# Biped_Motor_Control_Board.net
KiCad netlist of a schematic drawn in EasyEDA
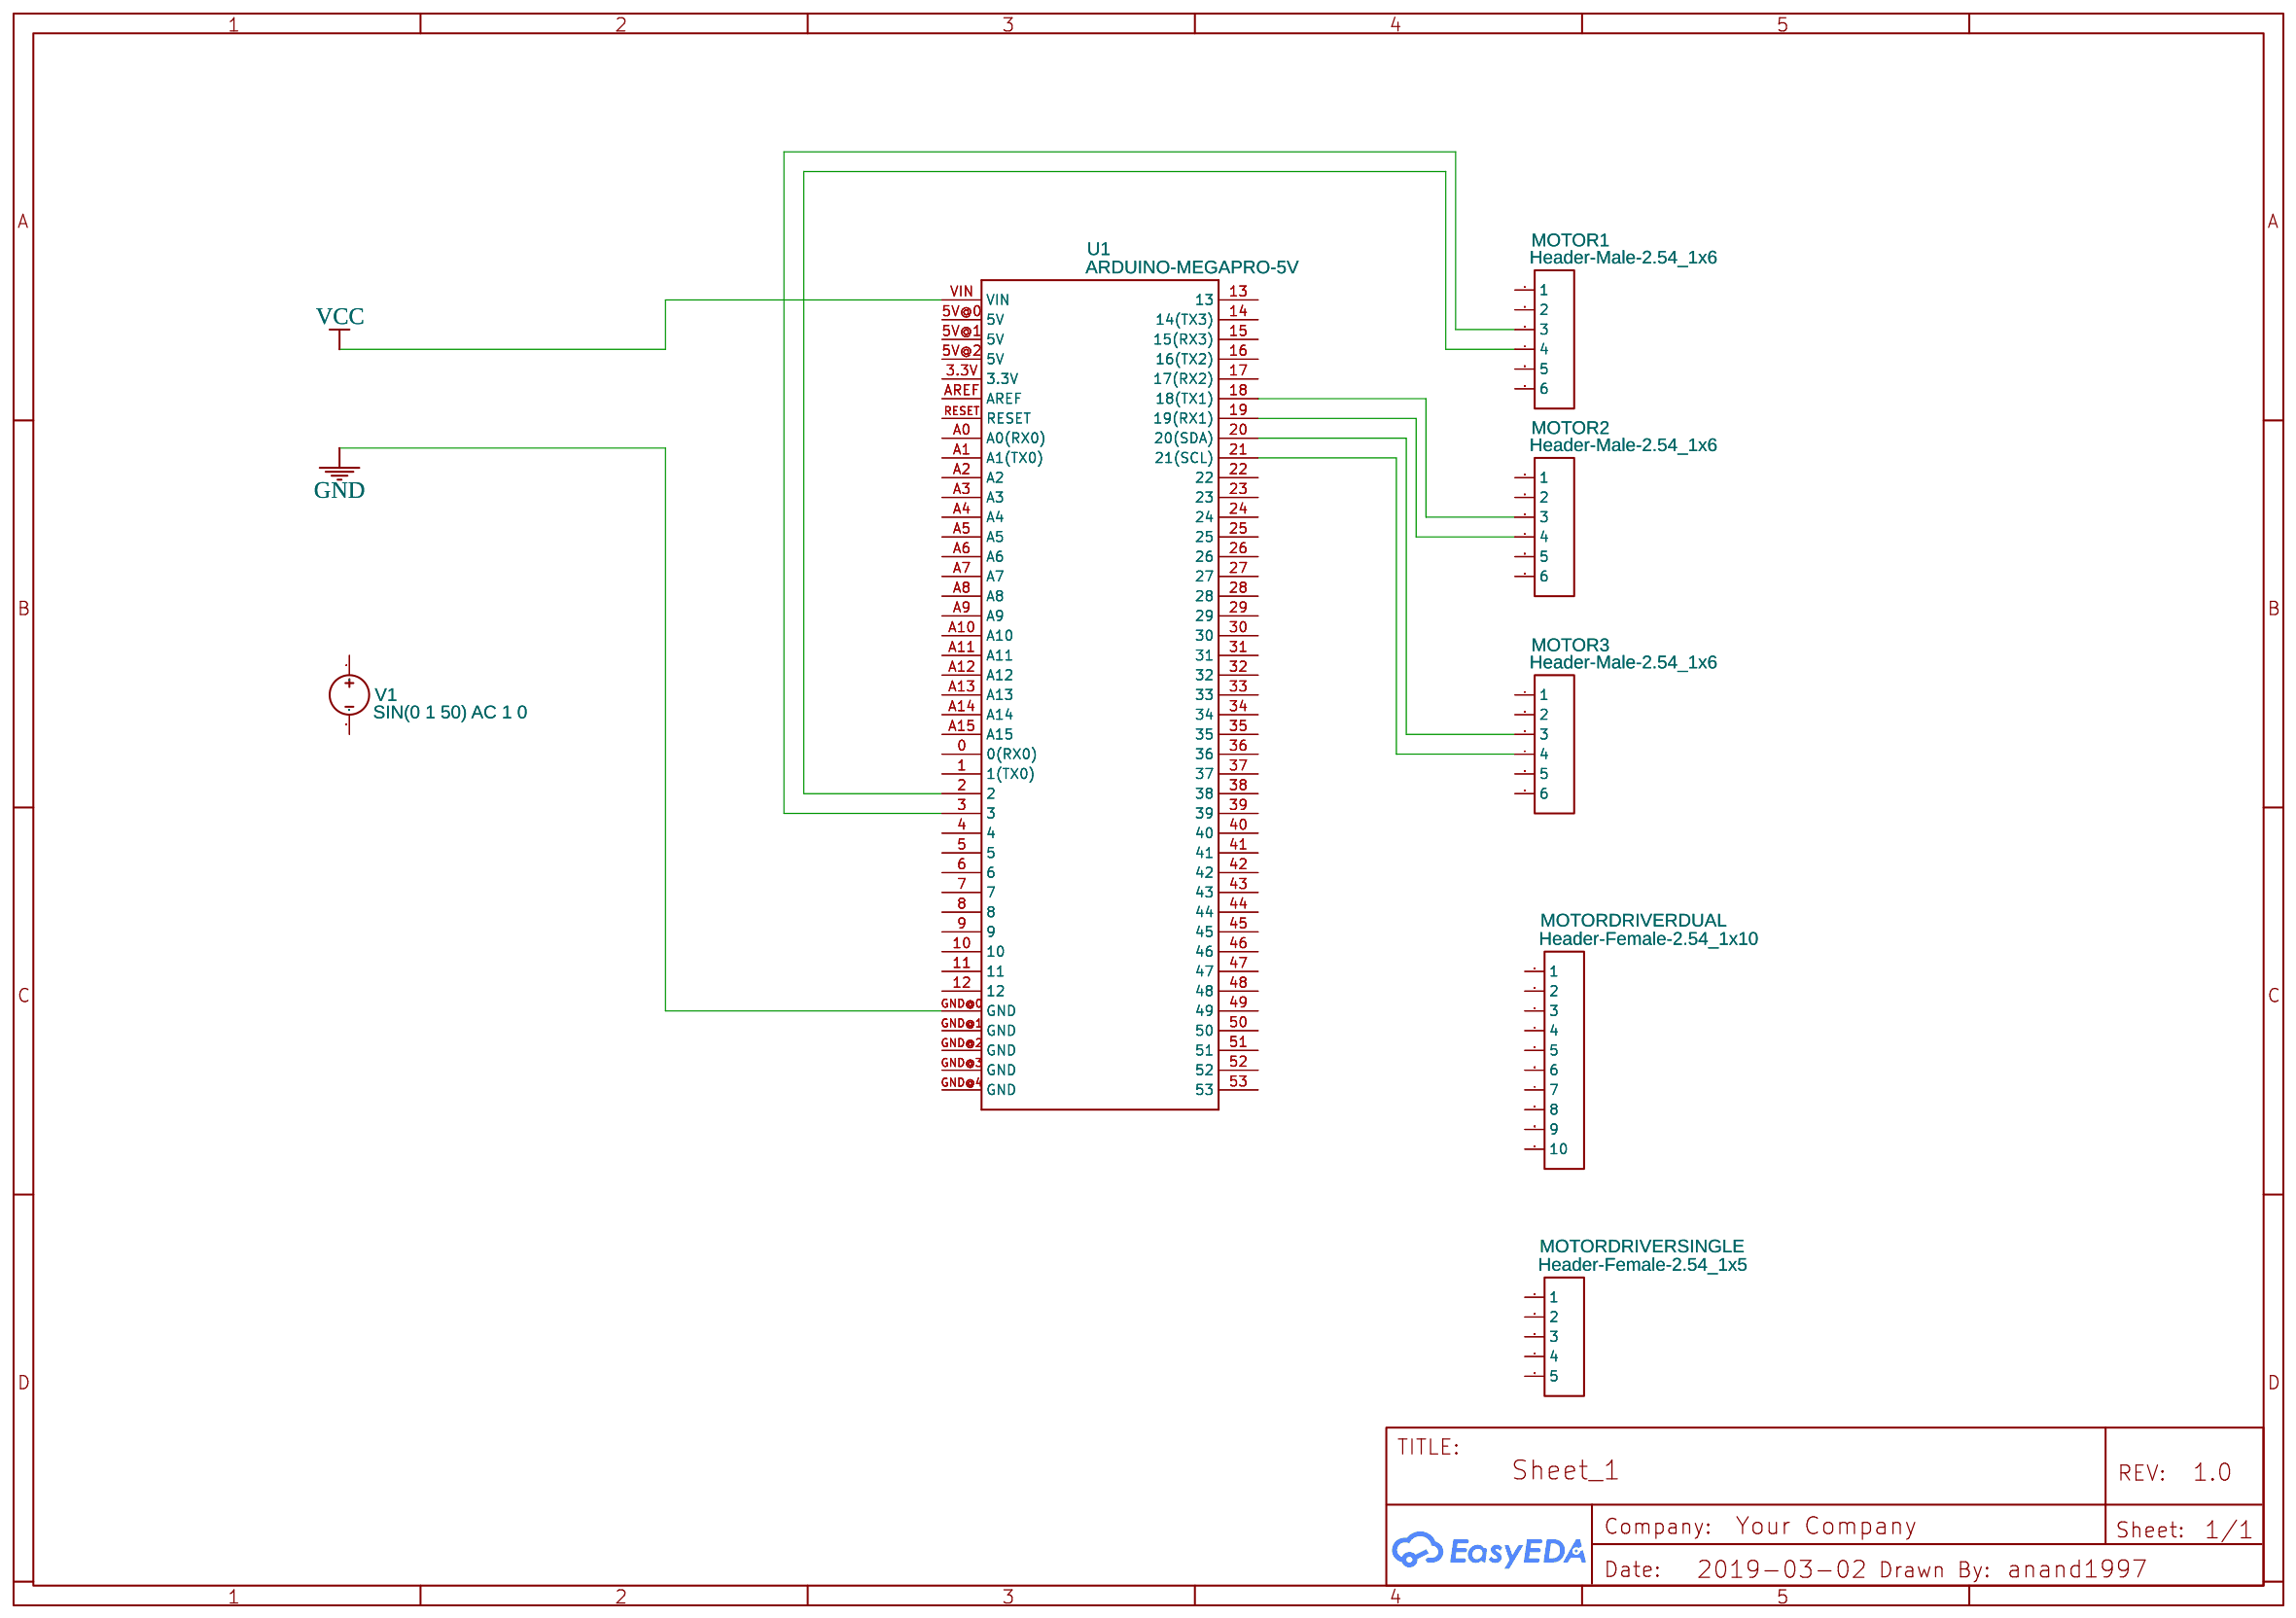
[diagram p0: schematic sheet]

(export (version "E")
  (design (tool "Eeschema 10.0.6"))
  (components
    (comp (ref "MOTOR1")
      (value "Header-Male-2.54_1x6")
      (fields (field (name "BOM_Supplier Part") "C37208"))
      (libsource (lib "") (part "Unknown_775_165"))
    )
    (comp (ref "MOTOR2")
      (value "Header-Male-2.54_1x6")
      (fields (field (name "BOM_Supplier Part") "C37208"))
      (libsource (lib "") (part "Unknown_775_260"))
    )
    (comp (ref "MOTOR3")
      (value "Header-Male-2.54_1x6")
      (fields (field (name "BOM_Supplier Part") "C37208"))
      (libsource (lib "") (part "Unknown_775_370"))
    )
    (comp (ref "MOTORDRIVERDUAL")
      (value "Header-Female-2.54_1x10")
      (fields
        (field (name "BOM_Manufacturer Part") "2.54mm 1*10P Straight Female header Gold-plated")
        (field (name "BOM_Supplier Part") "C35445")
      )
      (libsource (lib "") (part "Unknown_780_530"))
    )
    (comp (ref "MOTORDRIVERSINGLE")
      (value "Header-Female-2.54_1x5")
      (fields
        (field (name "BOM_Manufacturer Part") "2.54mm 1*5p Female header")
        (field (name "BOM_Supplier Part") "C50950")
      )
      (libsource (lib "") (part "Unknown_780_670"))
    )
    (comp (ref "U1")
      (value "ARDUINO-MEGAPRO-5V")
      (fields (field (name "BOM_Manufacturer Part") "?"))
      (libsource (lib "") (part "Unknown_540_345"))
    )
    (comp (ref "V1")
      (value "SIN(0 1 50) AC 1 0")
      (fields (field (name "BOM_Manufacturer Part") "?"))
      (libsource (lib "") (part "Vsin"))
    )
  )
  (nets
    (net (code "1") (name "GND") (class "Default")
      (node (ref "U1") (pin "GND@0") (pinfunction "GND_GND@0") (pintype "unspecified"))
    )
    (net (code "2") (name "Net-(MOTOR1-Pad3)") (class "Default")
      (node (ref "MOTOR1") (pin "3") (pinfunction "3_3") (pintype "input"))
      (node (ref "U1") (pin "3") (pinfunction "3_3") (pintype "unspecified"))
    )
    (net (code "3") (name "Net-(MOTOR1-Pad4)") (class "Default")
      (node (ref "MOTOR1") (pin "4") (pinfunction "4_4") (pintype "input"))
      (node (ref "U1") (pin "2") (pinfunction "2_2") (pintype "unspecified"))
    )
    (net (code "4") (name "Net-(U1-18(TX1))") (class "Default")
      (node (ref "MOTOR2") (pin "3") (pinfunction "3_3") (pintype "input"))
      (node (ref "U1") (pin "18") (pinfunction "18(TX1)_18") (pintype "unspecified"))
    )
    (net (code "5") (name "Net-(U1-19(RX1))") (class "Default")
      (node (ref "MOTOR2") (pin "4") (pinfunction "4_4") (pintype "input"))
      (node (ref "U1") (pin "19") (pinfunction "19(RX1)_19") (pintype "unspecified"))
    )
    (net (code "6") (name "Net-(U1-20(SDA))") (class "Default")
      (node (ref "MOTOR3") (pin "3") (pinfunction "3_3") (pintype "input"))
      (node (ref "U1") (pin "20") (pinfunction "20(SDA)_20") (pintype "unspecified"))
    )
    (net (code "7") (name "Net-(U1-21(SCL))") (class "Default")
      (node (ref "MOTOR3") (pin "4") (pinfunction "4_4") (pintype "input"))
      (node (ref "U1") (pin "21") (pinfunction "21(SCL)_21") (pintype "unspecified"))
    )
    (net (code "8") (name "VCC") (class "Default")
      (node (ref "U1") (pin "VIN") (pinfunction "VIN_VIN") (pintype "unspecified"))
    )
    (net (code "9") (name "unconnected-(MOTOR1-Pad1)") (class "Default")
      (node (ref "MOTOR1") (pin "1") (pinfunction "1_1") (pintype "input"))
    )
    (net (code "10") (name "unconnected-(MOTOR1-Pad2)") (class "Default")
      (node (ref "MOTOR1") (pin "2") (pinfunction "2_2") (pintype "input"))
    )
    (net (code "11") (name "unconnected-(MOTOR1-Pad5)") (class "Default")
      (node (ref "MOTOR1") (pin "5") (pinfunction "5_5") (pintype "input"))
    )
    (net (code "12") (name "unconnected-(MOTOR1-Pad6)") (class "Default")
      (node (ref "MOTOR1") (pin "6") (pinfunction "6_6") (pintype "input"))
    )
    (net (code "13") (name "unconnected-(MOTOR2-Pad1)") (class "Default")
      (node (ref "MOTOR2") (pin "1") (pinfunction "1_1") (pintype "input"))
    )
    (net (code "14") (name "unconnected-(MOTOR2-Pad2)") (class "Default")
      (node (ref "MOTOR2") (pin "2") (pinfunction "2_2") (pintype "input"))
    )
    (net (code "15") (name "unconnected-(MOTOR2-Pad5)") (class "Default")
      (node (ref "MOTOR2") (pin "5") (pinfunction "5_5") (pintype "input"))
    )
    (net (code "16") (name "unconnected-(MOTOR2-Pad6)") (class "Default")
      (node (ref "MOTOR2") (pin "6") (pinfunction "6_6") (pintype "input"))
    )
    (net (code "17") (name "unconnected-(MOTOR3-Pad1)") (class "Default")
      (node (ref "MOTOR3") (pin "1") (pinfunction "1_1") (pintype "input"))
    )
    (net (code "18") (name "unconnected-(MOTOR3-Pad2)") (class "Default")
      (node (ref "MOTOR3") (pin "2") (pinfunction "2_2") (pintype "input"))
    )
    (net (code "19") (name "unconnected-(MOTOR3-Pad5)") (class "Default")
      (node (ref "MOTOR3") (pin "5") (pinfunction "5_5") (pintype "input"))
    )
    (net (code "20") (name "unconnected-(MOTOR3-Pad6)") (class "Default")
      (node (ref "MOTOR3") (pin "6") (pinfunction "6_6") (pintype "input"))
    )
    (net (code "21") (name "unconnected-(MOTORDRIVERDUAL-Pad1)") (class "Default")
      (node (ref "MOTORDRIVERDUAL") (pin "1") (pinfunction "1_1") (pintype "input"))
    )
    (net (code "22") (name "unconnected-(MOTORDRIVERDUAL-Pad2)") (class "Default")
      (node (ref "MOTORDRIVERDUAL") (pin "2") (pinfunction "2_2") (pintype "input"))
    )
    (net (code "23") (name "unconnected-(MOTORDRIVERDUAL-Pad3)") (class "Default")
      (node (ref "MOTORDRIVERDUAL") (pin "3") (pinfunction "3_3") (pintype "input"))
    )
    (net (code "24") (name "unconnected-(MOTORDRIVERDUAL-Pad4)") (class "Default")
      (node (ref "MOTORDRIVERDUAL") (pin "4") (pinfunction "4_4") (pintype "input"))
    )
    (net (code "25") (name "unconnected-(MOTORDRIVERDUAL-Pad5)") (class "Default")
      (node (ref "MOTORDRIVERDUAL") (pin "5") (pinfunction "5_5") (pintype "input"))
    )
    (net (code "26") (name "unconnected-(MOTORDRIVERDUAL-Pad6)") (class "Default")
      (node (ref "MOTORDRIVERDUAL") (pin "6") (pinfunction "6_6") (pintype "input"))
    )
    (net (code "27") (name "unconnected-(MOTORDRIVERDUAL-Pad7)") (class "Default")
      (node (ref "MOTORDRIVERDUAL") (pin "7") (pinfunction "7_7") (pintype "input"))
    )
    (net (code "28") (name "unconnected-(MOTORDRIVERDUAL-Pad8)") (class "Default")
      (node (ref "MOTORDRIVERDUAL") (pin "8") (pinfunction "8_8") (pintype "input"))
    )
    (net (code "29") (name "unconnected-(MOTORDRIVERDUAL-Pad9)") (class "Default")
      (node (ref "MOTORDRIVERDUAL") (pin "9") (pinfunction "9_9") (pintype "input"))
    )
    (net (code "30") (name "unconnected-(MOTORDRIVERDUAL-Pad10)") (class "Default")
      (node (ref "MOTORDRIVERDUAL") (pin "10") (pinfunction "10_10") (pintype "input"))
    )
    (net (code "31") (name "unconnected-(MOTORDRIVERSINGLE-Pad1)") (class "Default")
      (node (ref "MOTORDRIVERSINGLE") (pin "1") (pinfunction "1_1") (pintype "input"))
    )
    (net (code "32") (name "unconnected-(MOTORDRIVERSINGLE-Pad2)") (class "Default")
      (node (ref "MOTORDRIVERSINGLE") (pin "2") (pinfunction "2_2") (pintype "input"))
    )
    (net (code "33") (name "unconnected-(MOTORDRIVERSINGLE-Pad3)") (class "Default")
      (node (ref "MOTORDRIVERSINGLE") (pin "3") (pinfunction "3_3") (pintype "input"))
    )
    (net (code "34") (name "unconnected-(MOTORDRIVERSINGLE-Pad4)") (class "Default")
      (node (ref "MOTORDRIVERSINGLE") (pin "4") (pinfunction "4_4") (pintype "input"))
    )
    (net (code "35") (name "unconnected-(MOTORDRIVERSINGLE-Pad5)") (class "Default")
      (node (ref "MOTORDRIVERSINGLE") (pin "5") (pinfunction "5_5") (pintype "input"))
    )
    (net (code "36") (name "unconnected-(U1-0(RX0)-Pad0)") (class "Default")
      (node (ref "U1") (pin "0") (pinfunction "0(RX0)_0") (pintype "unspecified"))
    )
    (net (code "37") (name "unconnected-(U1-1(TX0)-Pad1)") (class "Default")
      (node (ref "U1") (pin "1") (pinfunction "1(TX0)_1") (pintype "unspecified"))
    )
    (net (code "38") (name "unconnected-(U1-5V-Pad5V@0)") (class "Default")
      (node (ref "U1") (pin "5V@0") (pinfunction "5V_5V@0") (pintype "unspecified"))
    )
    (net (code "39") (name "unconnected-(U1-5V-Pad5V@1)") (class "Default")
      (node (ref "U1") (pin "5V@1") (pinfunction "5V_5V@1") (pintype "unspecified"))
    )
    (net (code "40") (name "unconnected-(U1-5V-Pad5V@2)") (class "Default")
      (node (ref "U1") (pin "5V@2") (pinfunction "5V_5V@2") (pintype "unspecified"))
    )
    (net (code "41") (name "unconnected-(U1-14(TX3)-Pad14)") (class "Default")
      (node (ref "U1") (pin "14") (pinfunction "14(TX3)_14") (pintype "unspecified"))
    )
    (net (code "42") (name "unconnected-(U1-15(RX3)-Pad15)") (class "Default")
      (node (ref "U1") (pin "15") (pinfunction "15(RX3)_15") (pintype "unspecified"))
    )
    (net (code "43") (name "unconnected-(U1-16(TX2)-Pad16)") (class "Default")
      (node (ref "U1") (pin "16") (pinfunction "16(TX2)_16") (pintype "unspecified"))
    )
    (net (code "44") (name "unconnected-(U1-17(RX2)-Pad17)") (class "Default")
      (node (ref "U1") (pin "17") (pinfunction "17(RX2)_17") (pintype "unspecified"))
    )
    (net (code "45") (name "unconnected-(U1-A0(RX0)-PadA0)") (class "Default")
      (node (ref "U1") (pin "A0") (pinfunction "A0(RX0)_A0") (pintype "unspecified"))
    )
    (net (code "46") (name "unconnected-(U1-A1(TX0)-PadA1)") (class "Default")
      (node (ref "U1") (pin "A1") (pinfunction "A1(TX0)_A1") (pintype "unspecified"))
    )
    (net (code "47") (name "unconnected-(U1-GND-PadGND@1)") (class "Default")
      (node (ref "U1") (pin "GND@1") (pinfunction "GND_GND@1") (pintype "unspecified"))
    )
    (net (code "48") (name "unconnected-(U1-GND-PadGND@2)") (class "Default")
      (node (ref "U1") (pin "GND@2") (pinfunction "GND_GND@2") (pintype "unspecified"))
    )
    (net (code "49") (name "unconnected-(U1-GND-PadGND@3)") (class "Default")
      (node (ref "U1") (pin "GND@3") (pinfunction "GND_GND@3") (pintype "unspecified"))
    )
    (net (code "50") (name "unconnected-(U1-GND-PadGND@4)") (class "Default")
      (node (ref "U1") (pin "GND@4") (pinfunction "GND_GND@4") (pintype "unspecified"))
    )
    (net (code "51") (name "unconnected-(U1-Pad3.3V)") (class "Default")
      (node (ref "U1") (pin "3.3V") (pinfunction "3.3V_3.3V") (pintype "unspecified"))
    )
    (net (code "52") (name "unconnected-(U1-Pad4)") (class "Default")
      (node (ref "U1") (pin "4") (pinfunction "4_4") (pintype "unspecified"))
    )
    (net (code "53") (name "unconnected-(U1-Pad5)") (class "Default")
      (node (ref "U1") (pin "5") (pinfunction "5_5") (pintype "unspecified"))
    )
    (net (code "54") (name "unconnected-(U1-Pad6)") (class "Default")
      (node (ref "U1") (pin "6") (pinfunction "6_6") (pintype "unspecified"))
    )
    (net (code "55") (name "unconnected-(U1-Pad7)") (class "Default")
      (node (ref "U1") (pin "7") (pinfunction "7_7") (pintype "unspecified"))
    )
    (net (code "56") (name "unconnected-(U1-Pad8)") (class "Default")
      (node (ref "U1") (pin "8") (pinfunction "8_8") (pintype "unspecified"))
    )
    (net (code "57") (name "unconnected-(U1-Pad9)") (class "Default")
      (node (ref "U1") (pin "9") (pinfunction "9_9") (pintype "unspecified"))
    )
    (net (code "58") (name "unconnected-(U1-Pad10)") (class "Default")
      (node (ref "U1") (pin "10") (pinfunction "10_10") (pintype "unspecified"))
    )
    (net (code "59") (name "unconnected-(U1-Pad11)") (class "Default")
      (node (ref "U1") (pin "11") (pinfunction "11_11") (pintype "unspecified"))
    )
    (net (code "60") (name "unconnected-(U1-Pad12)") (class "Default")
      (node (ref "U1") (pin "12") (pinfunction "12_12") (pintype "unspecified"))
    )
    (net (code "61") (name "unconnected-(U1-Pad13)") (class "Default")
      (node (ref "U1") (pin "13") (pinfunction "13_13") (pintype "unspecified"))
    )
    (net (code "62") (name "unconnected-(U1-Pad22)") (class "Default")
      (node (ref "U1") (pin "22") (pinfunction "22_22") (pintype "unspecified"))
    )
    (net (code "63") (name "unconnected-(U1-Pad23)") (class "Default")
      (node (ref "U1") (pin "23") (pinfunction "23_23") (pintype "unspecified"))
    )
    (net (code "64") (name "unconnected-(U1-Pad24)") (class "Default")
      (node (ref "U1") (pin "24") (pinfunction "24_24") (pintype "unspecified"))
    )
    (net (code "65") (name "unconnected-(U1-Pad25)") (class "Default")
      (node (ref "U1") (pin "25") (pinfunction "25_25") (pintype "unspecified"))
    )
    (net (code "66") (name "unconnected-(U1-Pad26)") (class "Default")
      (node (ref "U1") (pin "26") (pinfunction "26_26") (pintype "unspecified"))
    )
    (net (code "67") (name "unconnected-(U1-Pad27)") (class "Default")
      (node (ref "U1") (pin "27") (pinfunction "27_27") (pintype "unspecified"))
    )
    (net (code "68") (name "unconnected-(U1-Pad28)") (class "Default")
      (node (ref "U1") (pin "28") (pinfunction "28_28") (pintype "unspecified"))
    )
    (net (code "69") (name "unconnected-(U1-Pad29)") (class "Default")
      (node (ref "U1") (pin "29") (pinfunction "29_29") (pintype "unspecified"))
    )
    (net (code "70") (name "unconnected-(U1-Pad30)") (class "Default")
      (node (ref "U1") (pin "30") (pinfunction "30_30") (pintype "unspecified"))
    )
    (net (code "71") (name "unconnected-(U1-Pad31)") (class "Default")
      (node (ref "U1") (pin "31") (pinfunction "31_31") (pintype "unspecified"))
    )
    (net (code "72") (name "unconnected-(U1-Pad32)") (class "Default")
      (node (ref "U1") (pin "32") (pinfunction "32_32") (pintype "unspecified"))
    )
    (net (code "73") (name "unconnected-(U1-Pad33)") (class "Default")
      (node (ref "U1") (pin "33") (pinfunction "33_33") (pintype "unspecified"))
    )
    (net (code "74") (name "unconnected-(U1-Pad34)") (class "Default")
      (node (ref "U1") (pin "34") (pinfunction "34_34") (pintype "unspecified"))
    )
    (net (code "75") (name "unconnected-(U1-Pad35)") (class "Default")
      (node (ref "U1") (pin "35") (pinfunction "35_35") (pintype "unspecified"))
    )
    (net (code "76") (name "unconnected-(U1-Pad36)") (class "Default")
      (node (ref "U1") (pin "36") (pinfunction "36_36") (pintype "unspecified"))
    )
    (net (code "77") (name "unconnected-(U1-Pad37)") (class "Default")
      (node (ref "U1") (pin "37") (pinfunction "37_37") (pintype "unspecified"))
    )
    (net (code "78") (name "unconnected-(U1-Pad38)") (class "Default")
      (node (ref "U1") (pin "38") (pinfunction "38_38") (pintype "unspecified"))
    )
    (net (code "79") (name "unconnected-(U1-Pad39)") (class "Default")
      (node (ref "U1") (pin "39") (pinfunction "39_39") (pintype "unspecified"))
    )
    (net (code "80") (name "unconnected-(U1-Pad40)") (class "Default")
      (node (ref "U1") (pin "40") (pinfunction "40_40") (pintype "unspecified"))
    )
    (net (code "81") (name "unconnected-(U1-Pad41)") (class "Default")
      (node (ref "U1") (pin "41") (pinfunction "41_41") (pintype "unspecified"))
    )
    (net (code "82") (name "unconnected-(U1-Pad42)") (class "Default")
      (node (ref "U1") (pin "42") (pinfunction "42_42") (pintype "unspecified"))
    )
    (net (code "83") (name "unconnected-(U1-Pad43)") (class "Default")
      (node (ref "U1") (pin "43") (pinfunction "43_43") (pintype "unspecified"))
    )
    (net (code "84") (name "unconnected-(U1-Pad44)") (class "Default")
      (node (ref "U1") (pin "44") (pinfunction "44_44") (pintype "unspecified"))
    )
    (net (code "85") (name "unconnected-(U1-Pad45)") (class "Default")
      (node (ref "U1") (pin "45") (pinfunction "45_45") (pintype "unspecified"))
    )
    (net (code "86") (name "unconnected-(U1-Pad46)") (class "Default")
      (node (ref "U1") (pin "46") (pinfunction "46_46") (pintype "unspecified"))
    )
    (net (code "87") (name "unconnected-(U1-Pad47)") (class "Default")
      (node (ref "U1") (pin "47") (pinfunction "47_47") (pintype "unspecified"))
    )
    (net (code "88") (name "unconnected-(U1-Pad48)") (class "Default")
      (node (ref "U1") (pin "48") (pinfunction "48_48") (pintype "unspecified"))
    )
    (net (code "89") (name "unconnected-(U1-Pad49)") (class "Default")
      (node (ref "U1") (pin "49") (pinfunction "49_49") (pintype "unspecified"))
    )
    (net (code "90") (name "unconnected-(U1-Pad50)") (class "Default")
      (node (ref "U1") (pin "50") (pinfunction "50_50") (pintype "unspecified"))
    )
    (net (code "91") (name "unconnected-(U1-Pad51)") (class "Default")
      (node (ref "U1") (pin "51") (pinfunction "51_51") (pintype "unspecified"))
    )
    (net (code "92") (name "unconnected-(U1-Pad52)") (class "Default")
      (node (ref "U1") (pin "52") (pinfunction "52_52") (pintype "unspecified"))
    )
    (net (code "93") (name "unconnected-(U1-Pad53)") (class "Default")
      (node (ref "U1") (pin "53") (pinfunction "53_53") (pintype "unspecified"))
    )
    (net (code "94") (name "unconnected-(U1-PadA2)") (class "Default")
      (node (ref "U1") (pin "A2") (pinfunction "A2_A2") (pintype "unspecified"))
    )
    (net (code "95") (name "unconnected-(U1-PadA3)") (class "Default")
      (node (ref "U1") (pin "A3") (pinfunction "A3_A3") (pintype "unspecified"))
    )
    (net (code "96") (name "unconnected-(U1-PadA4)") (class "Default")
      (node (ref "U1") (pin "A4") (pinfunction "A4_A4") (pintype "unspecified"))
    )
    (net (code "97") (name "unconnected-(U1-PadA5)") (class "Default")
      (node (ref "U1") (pin "A5") (pinfunction "A5_A5") (pintype "unspecified"))
    )
    (net (code "98") (name "unconnected-(U1-PadA6)") (class "Default")
      (node (ref "U1") (pin "A6") (pinfunction "A6_A6") (pintype "unspecified"))
    )
    (net (code "99") (name "unconnected-(U1-PadA7)") (class "Default")
      (node (ref "U1") (pin "A7") (pinfunction "A7_A7") (pintype "unspecified"))
    )
    (net (code "100") (name "unconnected-(U1-PadA8)") (class "Default")
      (node (ref "U1") (pin "A8") (pinfunction "A8_A8") (pintype "unspecified"))
    )
    (net (code "101") (name "unconnected-(U1-PadA9)") (class "Default")
      (node (ref "U1") (pin "A9") (pinfunction "A9_A9") (pintype "unspecified"))
    )
    (net (code "102") (name "unconnected-(U1-PadA10)") (class "Default")
      (node (ref "U1") (pin "A10") (pinfunction "A10_A10") (pintype "unspecified"))
    )
    (net (code "103") (name "unconnected-(U1-PadA11)") (class "Default")
      (node (ref "U1") (pin "A11") (pinfunction "A11_A11") (pintype "unspecified"))
    )
    (net (code "104") (name "unconnected-(U1-PadA12)") (class "Default")
      (node (ref "U1") (pin "A12") (pinfunction "A12_A12") (pintype "unspecified"))
    )
    (net (code "105") (name "unconnected-(U1-PadA13)") (class "Default")
      (node (ref "U1") (pin "A13") (pinfunction "A13_A13") (pintype "unspecified"))
    )
    (net (code "106") (name "unconnected-(U1-PadA14)") (class "Default")
      (node (ref "U1") (pin "A14") (pinfunction "A14_A14") (pintype "unspecified"))
    )
    (net (code "107") (name "unconnected-(U1-PadA15)") (class "Default")
      (node (ref "U1") (pin "A15") (pinfunction "A15_A15") (pintype "unspecified"))
    )
    (net (code "108") (name "unconnected-(U1-PadAREF)") (class "Default")
      (node (ref "U1") (pin "AREF") (pinfunction "AREF_AREF") (pintype "unspecified"))
    )
    (net (code "109") (name "unconnected-(U1-PadRESET)") (class "Default")
      (node (ref "U1") (pin "RESET") (pinfunction "RESET_RESET") (pintype "unspecified"))
    )
    (net (code "110") (name "unconnected-(V1-Pad1)") (class "Default")
      (node (ref "V1") (pin "1") (pinfunction "1_1") (pintype "unspecified"))
    )
    (net (code "111") (name "unconnected-(V1-Pad2)") (class "Default")
      (node (ref "V1") (pin "2") (pinfunction "2_2") (pintype "unspecified"))
    )
  )
)
